# Sheet_sanya.net
KiCad netlist of a schematic drawn in Altium Designer
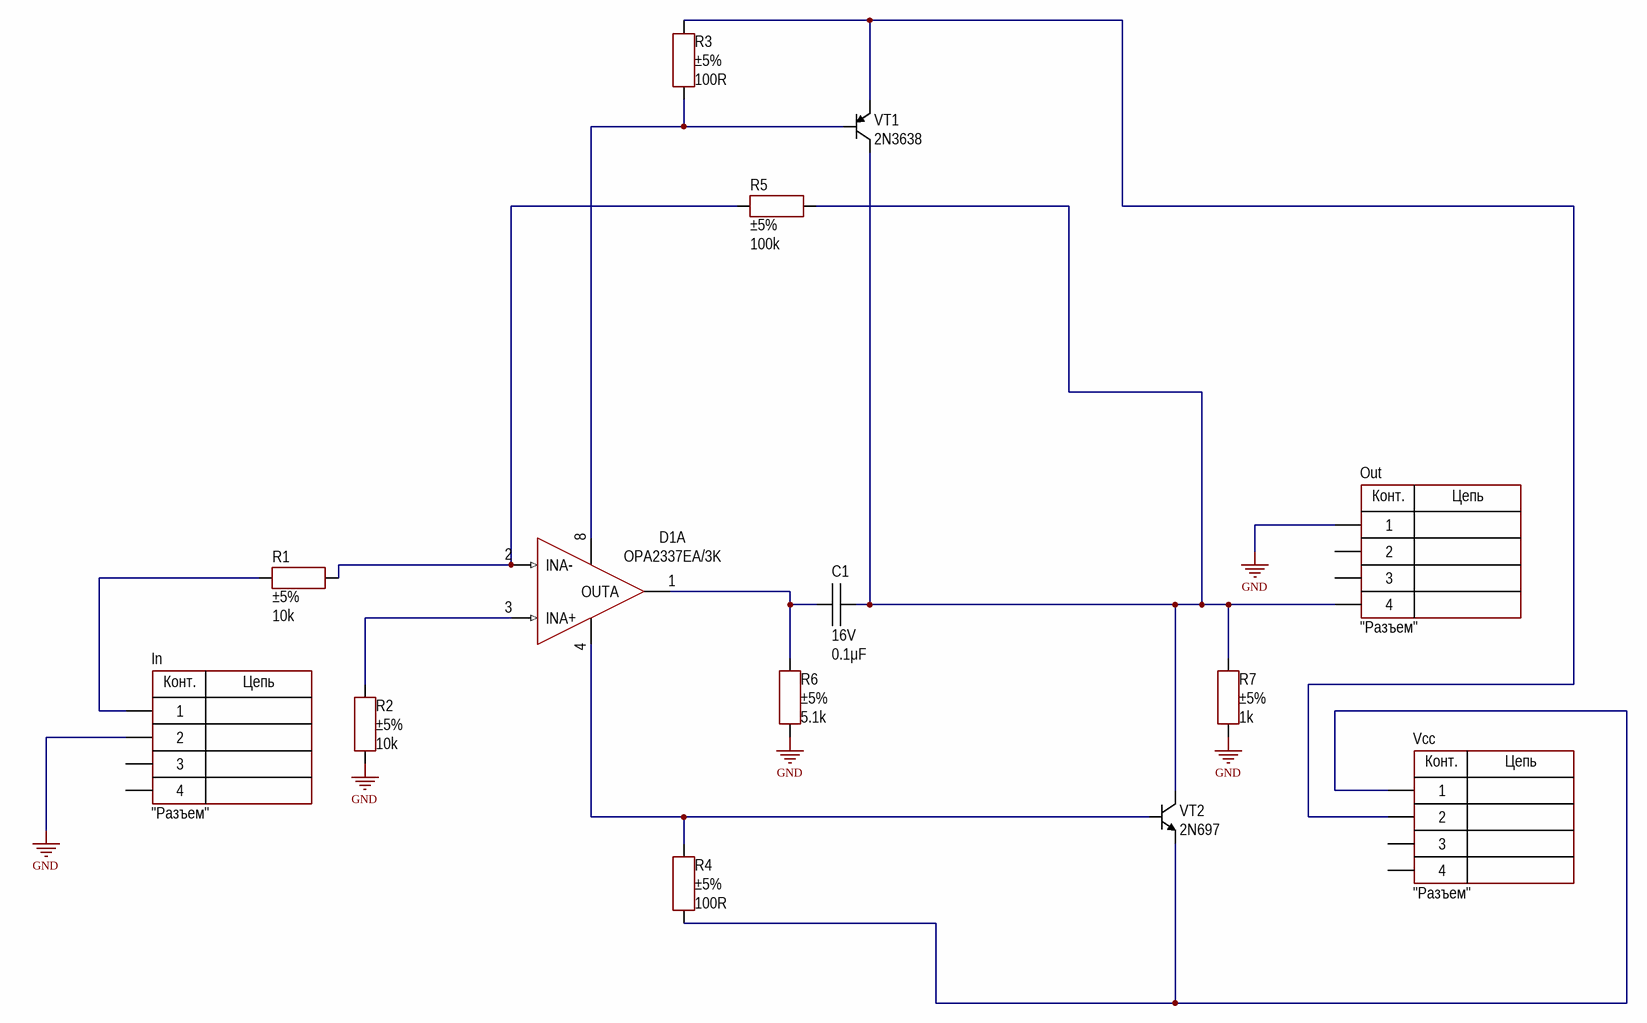
[diagram p0: Sheet(sanya).SchDoc]

(export (version "E")
  (design (tool "Eeschema 10.0.6"))
  (components
    (comp (ref "C1")
      (value "0.1μF")
      (footprint "CAP: 0201")
      (fields
        (field (name "MANUFACTURER") "Yageo")
        (field (name "PARTNUMBER") "CC0201KRX7R7BB103")
        (field (name "VALUEMANUFACTURERPARTNUMBER") "Ceramic capacitor, 0.1μF, X7R, ±10%, 16V, 0201, -55...+125°C")
        (field (name "VOLTAGE") "16V")
      )
      (libsource (lib "Capacitor") (part "Ceramic_0201"))
    )
    (comp (ref "D1")
      (value "~")
      (footprint "SOT23-8")
      (description "OP amplifier")
      (fields
        (field (name "MANUFACTURER") "Texas Instruments")
        (field (name "VALUEMANUFACTURERPARTNUMBER") "IC op amplifier, Rail-to-Rail, 3 MHz, 2.7...5.5V, -40...+125°C, SOT23-5")
        (field (name "PARTNUMBER") "OPA2337EA/3K")
      )
      (libsource (lib "IC. Amplifier") (part "OPA2337EA/3K"))
    )
    (comp (ref "In")
      (value "~")
      (footprint "CON: SM04B-GHS")
      (fields
        (field (name "MANUFACTURER") "JST")
        (field (name "VALUEMANUFACTURERPARTNUMBER") "Connector, 4pin, 1.25mm, 50VDC, 1A")
        (field (name "PARTNUMBER") "SM04B-GHS")
        (field (name "COMMENTTEXT") "\"Разъем\"")
      )
      (libsource (lib "Connector") (part "Connector_SM04B"))
    )
    (comp (ref "Out")
      (value "~")
      (footprint "CON: SM04B-GHS")
      (fields
        (field (name "MANUFACTURER") "JST")
        (field (name "VALUEMANUFACTURERPARTNUMBER") "Connector, 4pin, 1.25mm, 50VDC, 1A")
        (field (name "PARTNUMBER") "SM04B-GHS")
        (field (name "COMMENTTEXT") "\"Разъем\"")
      )
      (libsource (lib "Connector") (part "Connector_SM04B"))
    )
    (comp (ref "R1")
      (value "10k")
      (footprint "RES: 0402")
      (fields
        (field (name "MANUFACTURER") "Yageo")
        (field (name "PARTNUMBER") "RC0402JR-07100RL")
        (field (name "VALUEMANUFACTURERPARTNUMBER") "Resistor film, 10k, ±5%, 0402, 0.063W, -55...+125°C")
        (field (name "TOLERANCE") "±5%")
      )
      (libsource (lib "") (part "Resistor_0402_1"))
    )
    (comp (ref "R2")
      (value "10k")
      (footprint "RES: 0402")
      (fields
        (field (name "MANUFACTURER") "Yageo")
        (field (name "PARTNUMBER") "RC0402JR-07100RL")
        (field (name "VALUEMANUFACTURERPARTNUMBER") "Resistor film, 10k, ±5%, 0402, 0.063W, -55...+125°C")
        (field (name "TOLERANCE") "±5%")
      )
      (libsource (lib "Resistor") (part "Resistor_0402"))
    )
    (comp (ref "R3")
      (value "100R")
      (footprint "RES: 0402")
      (fields
        (field (name "MANUFACTURER") "Yageo")
        (field (name "PARTNUMBER") "RC0402JR-07100RL")
        (field (name "VALUEMANUFACTURERPARTNUMBER") "Resistor film, 100R, ±5%, 0402, 0.063W, -55...+125°C")
        (field (name "TOLERANCE") "±5%")
      )
      (libsource (lib "Resistor") (part "Resistor_0402"))
    )
    (comp (ref "R4")
      (value "100R")
      (footprint "RES: 0402")
      (fields
        (field (name "MANUFACTURER") "Yageo")
        (field (name "PARTNUMBER") "RC0402JR-07100RL")
        (field (name "VALUEMANUFACTURERPARTNUMBER") "Resistor film, 100R, ±5%, 0402, 0.063W, -55...+125°C")
        (field (name "TOLERANCE") "±5%")
      )
      (libsource (lib "") (part "Resistor_0402_2"))
    )
    (comp (ref "R5")
      (value "100k")
      (footprint "RES: 0402")
      (fields
        (field (name "MANUFACTURER") "Yageo")
        (field (name "PARTNUMBER") "RC0402JR-07100RL")
        (field (name "VALUEMANUFACTURERPARTNUMBER") "Resistor film, 100k, ±5%, 0402, 0.063W, -55...+125°C")
        (field (name "TOLERANCE") "±5%")
      )
      (libsource (lib "") (part "Resistor_0402_3"))
    )
    (comp (ref "R6")
      (value "5.1k")
      (footprint "RES: 0402")
      (fields
        (field (name "MANUFACTURER") "Yageo")
        (field (name "PARTNUMBER") "RC0402JR-07100RL")
        (field (name "VALUEMANUFACTURERPARTNUMBER") "Resistor film, 5.1k, ±5%, 0402, 0.063W, -55...+125°C")
        (field (name "TOLERANCE") "±5%")
      )
      (libsource (lib "") (part "Resistor_0402_2"))
    )
    (comp (ref "R7")
      (value "1k")
      (footprint "RES: 0402")
      (fields
        (field (name "MANUFACTURER") "Yageo")
        (field (name "PARTNUMBER") "RC0402JR-07100RL")
        (field (name "VALUEMANUFACTURERPARTNUMBER") "Resistor film, 1k, ±5%, 0402, 0.063W, -55...+125°C")
        (field (name "TOLERANCE") "±5%")
      )
      (libsource (lib "") (part "Resistor_0402_2"))
    )
    (comp (ref "Vcc")
      (value "~")
      (footprint "CON: SM04B-GHS")
      (fields
        (field (name "MANUFACTURER") "JST")
        (field (name "VALUEMANUFACTURERPARTNUMBER") "Connector, 4pin, 1.25mm, 50VDC, 1A")
        (field (name "PARTNUMBER") "SM04B-GHS")
        (field (name "COMMENTTEXT") "\"Разъем\"")
      )
      (libsource (lib "Connector") (part "Connector_SM04B"))
    )
    (comp (ref "VT1")
      (value "~")
      (footprint "SOT23")
      (fields
        (field (name "MANUFACTURER") "ON Semiconductor")
        (field (name "VALUEMANUFACTURERPARTNUMBER") "PNP transistor, 45V, 100mA, 100MHz, 300mW, 0.65V, 220, SOT-23, -55...+125°C")
        (field (name "PARTNUMBER") "2N3638")
      )
      (libsource (lib "Transistor") (part "BJT_PNP_132"))
    )
    (comp (ref "VT2")
      (value "~")
      (footprint "SOT23")
      (fields
        (field (name "MANUFACTURER") "ON Semiconductor")
        (field (name "VALUEMANUFACTURERPARTNUMBER") "NPN transistor, 45V, 100mA, 100MHz, 300mW, 0.6V, 420, SOT-23, -55...+125°C")
        (field (name "PARTNUMBER") "2N697")
      )
      (libsource (lib "Transistor") (part "BJT_NPN_123"))
    )
  )
  (nets
    (net (code "1") (name "GND") (class "Default")
      (node (ref "In") (pin "2") (pinfunction "2_2") (pintype "passive"))
      (node (ref "Out") (pin "1") (pinfunction "1_1") (pintype "passive"))
      (node (ref "R2") (pin "1") (pinfunction "1_1") (pintype "passive"))
      (node (ref "R6") (pin "2") (pinfunction "2_2") (pintype "passive"))
      (node (ref "R7") (pin "2") (pinfunction "2_2") (pintype "passive"))
    )
    (net (code "2") (name "Net-(D1A-INA+)") (class "Default")
      (node (ref "D1") (pin "3") (pinfunction "INA+_3") (pintype "input"))
      (node (ref "R2") (pin "2") (pinfunction "2_2") (pintype "passive"))
    )
    (net (code "3") (name "Net-(D1A-INA-)") (class "Default")
      (node (ref "D1") (pin "2") (pinfunction "INA-_2") (pintype "input"))
      (node (ref "R1") (pin "2") (pinfunction "2_2") (pintype "passive"))
      (node (ref "R5") (pin "2") (pinfunction "2_2") (pintype "passive"))
    )
    (net (code "4") (name "Net-(D1A-OUTA)") (class "Default")
      (node (ref "C1") (pin "2") (pinfunction "2_2") (pintype "power_in"))
      (node (ref "D1") (pin "1") (pinfunction "OUTA_1") (pintype "power_in"))
      (node (ref "R6") (pin "1") (pinfunction "1_1") (pintype "passive"))
    )
    (net (code "5") (name "Net-(D1A-V+)") (class "Default")
      (node (ref "D1") (pin "8") (pinfunction "V+_8") (pintype "power_in"))
      (node (ref "R3") (pin "1") (pinfunction "1_1") (pintype "passive"))
      (node (ref "VT1") (pin "1") (pinfunction "B_1") (pintype "passive"))
    )
    (net (code "6") (name "Net-(D1A-V-)") (class "Default")
      (node (ref "D1") (pin "4") (pinfunction "V-_4") (pintype "power_in"))
      (node (ref "R4") (pin "1") (pinfunction "1_1") (pintype "passive"))
      (node (ref "VT2") (pin "1") (pinfunction "B_1") (pintype "passive"))
    )
    (net (code "7") (name "Net-(In-Pad1)") (class "Default")
      (node (ref "In") (pin "1") (pinfunction "1_1") (pintype "passive"))
      (node (ref "R1") (pin "1") (pinfunction "1_1") (pintype "passive"))
    )
    (net (code "8") (name "Net-(VT1-C)") (class "Default")
      (node (ref "C1") (pin "1") (pinfunction "1_1") (pintype "power_in"))
      (node (ref "Out") (pin "4") (pinfunction "4_4") (pintype "power_in"))
      (node (ref "R5") (pin "1") (pinfunction "1_1") (pintype "passive"))
      (node (ref "R7") (pin "1") (pinfunction "1_1") (pintype "passive"))
      (node (ref "VT1") (pin "2") (pinfunction "C_2") (pintype "passive"))
      (node (ref "VT2") (pin "2") (pinfunction "C_2") (pintype "passive"))
    )
    (net (code "9") (name "Net-(VT1-E)") (class "Default")
      (node (ref "R3") (pin "2") (pinfunction "2_2") (pintype "passive"))
      (node (ref "VT1") (pin "3") (pinfunction "E_3") (pintype "passive"))
      (node (ref "Vcc") (pin "2") (pinfunction "2_2") (pintype "passive"))
    )
    (net (code "10") (name "Net-(VT2-E)") (class "Default")
      (node (ref "R4") (pin "2") (pinfunction "2_2") (pintype "passive"))
      (node (ref "VT2") (pin "3") (pinfunction "E_3") (pintype "passive"))
      (node (ref "Vcc") (pin "1") (pinfunction "1_1") (pintype "passive"))
    )
    (net (code "11") (name "unconnected-(In-Pad3)") (class "Default")
      (node (ref "In") (pin "3") (pinfunction "3_3") (pintype "power_in"))
    )
    (net (code "12") (name "unconnected-(In-Pad4)") (class "Default")
      (node (ref "In") (pin "4") (pinfunction "4_4") (pintype "power_in"))
    )
    (net (code "13") (name "unconnected-(Out-Pad2)") (class "Default")
      (node (ref "Out") (pin "2") (pinfunction "2_2") (pintype "passive"))
    )
    (net (code "14") (name "unconnected-(Out-Pad3)") (class "Default")
      (node (ref "Out") (pin "3") (pinfunction "3_3") (pintype "power_in"))
    )
    (net (code "15") (name "unconnected-(Vcc-Pad3)") (class "Default")
      (node (ref "Vcc") (pin "3") (pinfunction "3_3") (pintype "power_in"))
    )
    (net (code "16") (name "unconnected-(Vcc-Pad4)") (class "Default")
      (node (ref "Vcc") (pin "4") (pinfunction "4_4") (pintype "power_in"))
    )
  )
)
